# analog.net
KiCad netlist of a schematic drawn in Altium Designer
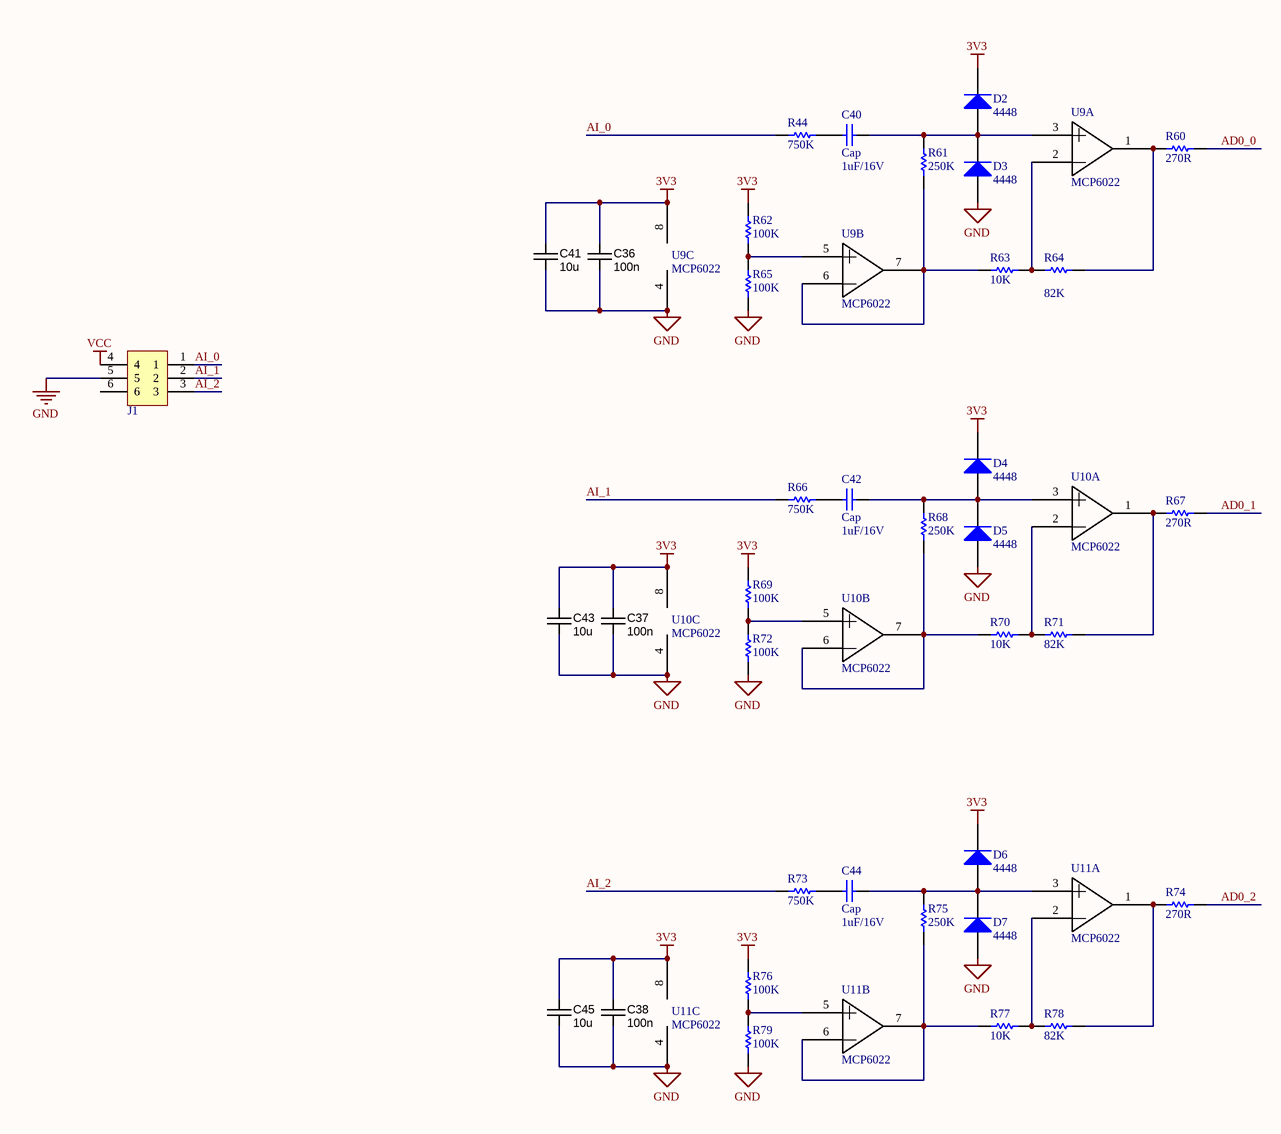
[diagram p0: analog.SchDoc]

(export (version "E")
  (design (tool "Eeschema 10.0.6"))
  (components
    (comp (ref "C36")
      (value "100n")
      (footprint "CAPC1005L")
      (description "Capacitor SMD")
      (fields (field (name "TOLERANCE") "?0%"))
      (libsource (lib "PBL - Capacitors") (part "CAPC_100n_0805"))
    )
    (comp (ref "C37")
      (value "100n")
      (footprint "CAPC1005L")
      (description "Capacitor SMD")
      (fields (field (name "TOLERANCE") "?0%"))
      (libsource (lib "PBL - Capacitors") (part "CAPC_100n_0805"))
    )
    (comp (ref "C38")
      (value "100n")
      (footprint "CAPC1005L")
      (description "Capacitor SMD")
      (fields (field (name "TOLERANCE") "?0%"))
      (libsource (lib "PBL - Capacitors") (part "CAPC_100n_0805"))
    )
    (comp (ref "C40")
      (value "Cap")
      (footprint "CAPC1005L")
      (description "Capacitor SMD")
      (fields (field (name "ALTIUM_VALUE") "1uF/16V") (field (name "PUBLISHER") "Altium Limited"))
      (libsource (lib "Miscellaneous Devices") (part "Cap"))
    )
    (comp (ref "C41")
      (value "10u")
      (footprint "CAPC2012N")
      (description "Capacitor SMD")
      (fields (field (name "TOLERANCE") "?0%"))
      (libsource (lib "PBL - Capacitors") (part "CAPC_100n_0805"))
    )
    (comp (ref "C42")
      (value "Cap")
      (footprint "CAPC1005L")
      (description "Capacitor SMD")
      (fields (field (name "ALTIUM_VALUE") "1uF/16V") (field (name "PUBLISHER") "Altium Limited"))
      (libsource (lib "Miscellaneous Devices") (part "Cap"))
    )
    (comp (ref "C43")
      (value "10u")
      (footprint "CAPC2012N")
      (description "Capacitor SMD")
      (fields (field (name "TOLERANCE") "?0%"))
      (libsource (lib "PBL - Capacitors") (part "CAPC_100n_0805"))
    )
    (comp (ref "C44")
      (value "Cap")
      (footprint "CAPC1005L")
      (description "Capacitor SMD")
      (fields (field (name "ALTIUM_VALUE") "1uF/16V") (field (name "PUBLISHER") "Altium Limited"))
      (libsource (lib "Miscellaneous Devices") (part "Cap"))
    )
    (comp (ref "C45")
      (value "10u")
      (footprint "CAPC2012N")
      (description "Capacitor SMD")
      (fields (field (name "TOLERANCE") "?0%"))
      (libsource (lib "PBL - Capacitors") (part "CAPC_100n_0805"))
    )
    (comp (ref "D2")
      (value "4448")
      (footprint "SOD323")
      (description "High Conductance Fast Diode")
      (fields (field (name "PUBLISHER") "Altium Limited"))
      (libsource (lib "Miscellaneous Devices") (part "Diode 1N4448"))
    )
    (comp (ref "D3")
      (value "4448")
      (footprint "SOD323")
      (description "High Conductance Fast Diode")
      (fields (field (name "PUBLISHER") "Altium Limited"))
      (libsource (lib "Miscellaneous Devices") (part "Diode 1N4448"))
    )
    (comp (ref "D4")
      (value "4448")
      (footprint "SOD323")
      (description "High Conductance Fast Diode")
      (fields (field (name "PUBLISHER") "Altium Limited"))
      (libsource (lib "Miscellaneous Devices") (part "Diode 1N4448"))
    )
    (comp (ref "D5")
      (value "4448")
      (footprint "SOD323")
      (description "High Conductance Fast Diode")
      (fields (field (name "PUBLISHER") "Altium Limited"))
      (libsource (lib "Miscellaneous Devices") (part "Diode 1N4448"))
    )
    (comp (ref "D6")
      (value "4448")
      (footprint "SOD323")
      (description "High Conductance Fast Diode")
      (fields (field (name "PUBLISHER") "Altium Limited"))
      (libsource (lib "Miscellaneous Devices") (part "Diode 1N4448"))
    )
    (comp (ref "D7")
      (value "4448")
      (footprint "SOD323")
      (description "High Conductance Fast Diode")
      (fields (field (name "PUBLISHER") "Altium Limited"))
      (libsource (lib "Miscellaneous Devices") (part "Diode 1N4448"))
    )
    (comp (ref "J1")
      (value "2X6du pont-2.0mm-6line to 90der")
      (footprint "HDR2X3 - duplicate-6-line 90 der")
      (libsource (lib "All_Library1") (part "2X6du pont-2.0mm-6line to 90der"))
    )
    (comp (ref "R44")
      (value "750K")
      (footprint "RESC1005L")
      (description "Resistor SMD")
      (fields (field (name "PUBLISHER") "Altium Limited"))
      (libsource (lib "Miscellaneous Devices") (part "Res1"))
    )
    (comp (ref "R60")
      (value "270R")
      (footprint "RESC1005L")
      (description "Resistor SMD")
      (fields (field (name "PUBLISHER") "Altium Limited"))
      (libsource (lib "Miscellaneous Devices") (part "Res1"))
    )
    (comp (ref "R61")
      (value "250K")
      (footprint "RESC1005L")
      (description "Resistor SMD")
      (fields (field (name "PUBLISHER") "Altium Limited"))
      (libsource (lib "Miscellaneous Devices") (part "Res1"))
    )
    (comp (ref "R62")
      (value "100K")
      (footprint "RESC1005L")
      (description "Resistor SMD")
      (fields (field (name "PUBLISHER") "Altium Limited"))
      (libsource (lib "Miscellaneous Devices") (part "Res1"))
    )
    (comp (ref "R63")
      (value "10K")
      (footprint "RESC1005L")
      (description "Resistor SMD")
      (fields (field (name "PUBLISHER") "Altium Limited"))
      (libsource (lib "Miscellaneous Devices") (part "Res1"))
    )
    (comp (ref "R64")
      (value "82K")
      (footprint "RESC1005L")
      (description "Resistor SMD")
      (fields (field (name "PUBLISHER") "Altium Limited"))
      (libsource (lib "Miscellaneous Devices") (part "Res1"))
    )
    (comp (ref "R65")
      (value "100K")
      (footprint "RESC1005L")
      (description "Resistor SMD")
      (fields (field (name "PUBLISHER") "Altium Limited"))
      (libsource (lib "Miscellaneous Devices") (part "Res1"))
    )
    (comp (ref "R66")
      (value "750K")
      (footprint "RESC1005L")
      (description "Resistor SMD")
      (fields (field (name "PUBLISHER") "Altium Limited"))
      (libsource (lib "Miscellaneous Devices") (part "Res1"))
    )
    (comp (ref "R67")
      (value "270R")
      (footprint "RESC1005L")
      (description "Resistor SMD")
      (fields (field (name "PUBLISHER") "Altium Limited"))
      (libsource (lib "Miscellaneous Devices") (part "Res1"))
    )
    (comp (ref "R68")
      (value "250K")
      (footprint "RESC1005L")
      (description "Resistor SMD")
      (fields (field (name "PUBLISHER") "Altium Limited"))
      (libsource (lib "Miscellaneous Devices") (part "Res1"))
    )
    (comp (ref "R69")
      (value "100K")
      (footprint "RESC1005L")
      (description "Resistor SMD")
      (fields (field (name "PUBLISHER") "Altium Limited"))
      (libsource (lib "Miscellaneous Devices") (part "Res1"))
    )
    (comp (ref "R70")
      (value "10K")
      (footprint "RESC1005L")
      (description "Resistor SMD")
      (fields (field (name "PUBLISHER") "Altium Limited"))
      (libsource (lib "Miscellaneous Devices") (part "Res1"))
    )
    (comp (ref "R71")
      (value "82K")
      (footprint "RESC1005L")
      (description "Resistor SMD")
      (fields (field (name "PUBLISHER") "Altium Limited"))
      (libsource (lib "Miscellaneous Devices") (part "Res1"))
    )
    (comp (ref "R72")
      (value "100K")
      (footprint "RESC1005L")
      (description "Resistor SMD")
      (fields (field (name "PUBLISHER") "Altium Limited"))
      (libsource (lib "Miscellaneous Devices") (part "Res1"))
    )
    (comp (ref "R73")
      (value "750K")
      (footprint "RESC1005L")
      (description "Resistor SMD")
      (fields (field (name "PUBLISHER") "Altium Limited"))
      (libsource (lib "Miscellaneous Devices") (part "Res1"))
    )
    (comp (ref "R74")
      (value "270R")
      (footprint "RESC1005L")
      (description "Resistor SMD")
      (fields (field (name "PUBLISHER") "Altium Limited"))
      (libsource (lib "Miscellaneous Devices") (part "Res1"))
    )
    (comp (ref "R75")
      (value "250K")
      (footprint "RESC1005L")
      (description "Resistor SMD")
      (fields (field (name "PUBLISHER") "Altium Limited"))
      (libsource (lib "Miscellaneous Devices") (part "Res1"))
    )
    (comp (ref "R76")
      (value "100K")
      (footprint "RESC1005L")
      (description "Resistor SMD")
      (fields (field (name "PUBLISHER") "Altium Limited"))
      (libsource (lib "Miscellaneous Devices") (part "Res1"))
    )
    (comp (ref "R77")
      (value "10K")
      (footprint "RESC1005L")
      (description "Resistor SMD")
      (fields (field (name "PUBLISHER") "Altium Limited"))
      (libsource (lib "Miscellaneous Devices") (part "Res1"))
    )
    (comp (ref "R78")
      (value "82K")
      (footprint "RESC1005L")
      (description "Resistor SMD")
      (fields (field (name "PUBLISHER") "Altium Limited"))
      (libsource (lib "Miscellaneous Devices") (part "Res1"))
    )
    (comp (ref "R79")
      (value "100K")
      (footprint "RESC1005L")
      (description "Resistor SMD")
      (fields (field (name "PUBLISHER") "Altium Limited"))
      (libsource (lib "Miscellaneous Devices") (part "Res1"))
    )
    (comp (ref "U9") (value "MCP6022") (footprint "TSSOP-ST8_N") (libsource (lib "Schlib1") (part "MCP6022")))
    (comp (ref "U10")
      (value "MCP6022")
      (footprint "TSSOP-ST8_N")
      (libsource (lib "Schlib1") (part "MCP6022"))
    )
    (comp (ref "U11")
      (value "MCP6022")
      (footprint "TSSOP-ST8_N")
      (libsource (lib "Schlib1") (part "MCP6022"))
    )
  )
  (nets
    (net (code "1") (name "/AD0_0") (class "Default")
      (node (ref "R60") (pin "2") (pinfunction "2_2") (pintype "passive"))
    )
    (net (code "2") (name "/AD0_1") (class "Default")
      (node (ref "R67") (pin "2") (pinfunction "2_2") (pintype "passive"))
    )
    (net (code "3") (name "/AD0_2") (class "Default")
      (node (ref "R74") (pin "2") (pinfunction "2_2") (pintype "passive"))
    )
    (net (code "4") (name "/AI_0") (class "Default")
      (node (ref "J1") (pin "1") (pinfunction "1_1") (pintype "passive"))
      (node (ref "R44") (pin "1") (pinfunction "1_1") (pintype "passive"))
    )
    (net (code "5") (name "/AI_1") (class "Default")
      (node (ref "J1") (pin "2") (pinfunction "2_2") (pintype "passive"))
      (node (ref "R66") (pin "1") (pinfunction "1_1") (pintype "passive"))
    )
    (net (code "6") (name "/AI_2") (class "Default")
      (node (ref "J1") (pin "3") (pinfunction "3_3") (pintype "passive"))
      (node (ref "R73") (pin "1") (pinfunction "1_1") (pintype "passive"))
    )
    (net (code "7") (name "3V3") (class "Default")
      (node (ref "C36") (pin "1") (pintype "passive"))
      (node (ref "C37") (pin "1") (pintype "passive"))
      (node (ref "C38") (pin "1") (pintype "passive"))
      (node (ref "C41") (pin "1") (pintype "passive"))
      (node (ref "C43") (pin "1") (pintype "passive"))
      (node (ref "C45") (pin "1") (pintype "passive"))
      (node (ref "D2") (pin "2") (pinfunction "K_2") (pintype "passive"))
      (node (ref "D4") (pin "2") (pinfunction "K_2") (pintype "passive"))
      (node (ref "D6") (pin "2") (pinfunction "K_2") (pintype "passive"))
      (node (ref "R62") (pin "2") (pinfunction "2_2") (pintype "passive"))
      (node (ref "R69") (pin "2") (pinfunction "2_2") (pintype "passive"))
      (node (ref "R76") (pin "2") (pinfunction "2_2") (pintype "passive"))
      (node (ref "U10") (pin "8") (pinfunction "VDD_8") (pintype "passive"))
      (node (ref "U11") (pin "8") (pinfunction "VDD_8") (pintype "passive"))
      (node (ref "U9") (pin "8") (pinfunction "VDD_8") (pintype "passive"))
    )
    (net (code "8") (name "GND") (class "Default")
      (node (ref "C36") (pin "2") (pintype "passive"))
      (node (ref "C37") (pin "2") (pintype "passive"))
      (node (ref "C38") (pin "2") (pintype "passive"))
      (node (ref "C41") (pin "2") (pintype "passive"))
      (node (ref "C43") (pin "2") (pintype "passive"))
      (node (ref "C45") (pin "2") (pintype "passive"))
      (node (ref "D3") (pin "1") (pinfunction "A_1") (pintype "passive"))
      (node (ref "D5") (pin "1") (pinfunction "A_1") (pintype "passive"))
      (node (ref "D7") (pin "1") (pinfunction "A_1") (pintype "passive"))
      (node (ref "J1") (pin "5") (pinfunction "5_5") (pintype "passive"))
      (node (ref "R65") (pin "1") (pinfunction "1_1") (pintype "passive"))
      (node (ref "R72") (pin "1") (pinfunction "1_1") (pintype "passive"))
      (node (ref "R79") (pin "1") (pinfunction "1_1") (pintype "passive"))
      (node (ref "U10") (pin "4") (pinfunction "GND_4") (pintype "passive"))
      (node (ref "U11") (pin "4") (pinfunction "GND_4") (pintype "passive"))
      (node (ref "U9") (pin "4") (pinfunction "GND_4") (pintype "passive"))
    )
    (net (code "9") (name "Net-(C40-Pad1)") (class "Default")
      (node (ref "C40") (pin "1") (pinfunction "1_1") (pintype "passive"))
      (node (ref "R44") (pin "2") (pinfunction "2_2") (pintype "passive"))
    )
    (net (code "10") (name "Net-(C42-Pad1)") (class "Default")
      (node (ref "C42") (pin "1") (pinfunction "1_1") (pintype "passive"))
      (node (ref "R66") (pin "2") (pinfunction "2_2") (pintype "passive"))
    )
    (net (code "11") (name "Net-(C44-Pad1)") (class "Default")
      (node (ref "C44") (pin "1") (pinfunction "1_1") (pintype "passive"))
      (node (ref "R73") (pin "2") (pinfunction "2_2") (pintype "passive"))
    )
    (net (code "12") (name "Net-(D2-A)") (class "Default")
      (node (ref "C40") (pin "2") (pinfunction "2_2") (pintype "passive"))
      (node (ref "D2") (pin "1") (pinfunction "A_1") (pintype "passive"))
      (node (ref "D3") (pin "2") (pinfunction "K_2") (pintype "passive"))
      (node (ref "R61") (pin "2") (pinfunction "2_2") (pintype "passive"))
      (node (ref "U9") (pin "3") (pinfunction "VINA+_3") (pintype "passive"))
    )
    (net (code "13") (name "Net-(D4-A)") (class "Default")
      (node (ref "C42") (pin "2") (pinfunction "2_2") (pintype "passive"))
      (node (ref "D4") (pin "1") (pinfunction "A_1") (pintype "passive"))
      (node (ref "D5") (pin "2") (pinfunction "K_2") (pintype "passive"))
      (node (ref "R68") (pin "2") (pinfunction "2_2") (pintype "passive"))
      (node (ref "U10") (pin "3") (pinfunction "VINA+_3") (pintype "passive"))
    )
    (net (code "14") (name "Net-(D6-A)") (class "Default")
      (node (ref "C44") (pin "2") (pinfunction "2_2") (pintype "passive"))
      (node (ref "D6") (pin "1") (pinfunction "A_1") (pintype "passive"))
      (node (ref "D7") (pin "2") (pinfunction "K_2") (pintype "passive"))
      (node (ref "R75") (pin "2") (pinfunction "2_2") (pintype "passive"))
      (node (ref "U11") (pin "3") (pinfunction "VINA+_3") (pintype "passive"))
    )
    (net (code "15") (name "Net-(U9A-VINA-)") (class "Default")
      (node (ref "R63") (pin "2") (pinfunction "2_2") (pintype "passive"))
      (node (ref "R64") (pin "1") (pinfunction "1_1") (pintype "passive"))
      (node (ref "U9") (pin "2") (pinfunction "VINA-_2") (pintype "passive"))
    )
    (net (code "16") (name "Net-(U9A-VOUTA)") (class "Default")
      (node (ref "R60") (pin "1") (pinfunction "1_1") (pintype "passive"))
      (node (ref "R64") (pin "2") (pinfunction "2_2") (pintype "passive"))
      (node (ref "U9") (pin "1") (pinfunction "VOUTA_1") (pintype "passive"))
    )
    (net (code "17") (name "Net-(U9B-VINB+)") (class "Default")
      (node (ref "R62") (pin "1") (pinfunction "1_1") (pintype "passive"))
      (node (ref "R65") (pin "2") (pinfunction "2_2") (pintype "passive"))
      (node (ref "U9") (pin "5") (pinfunction "VINB+_5") (pintype "passive"))
    )
    (net (code "18") (name "Net-(U9B-VINB-)") (class "Default")
      (node (ref "R61") (pin "1") (pinfunction "1_1") (pintype "passive"))
      (node (ref "R63") (pin "1") (pinfunction "1_1") (pintype "passive"))
      (node (ref "U9") (pin "6") (pinfunction "VINB-_6") (pintype "passive"))
      (node (ref "U9") (pin "7") (pinfunction "VOUTB_7") (pintype "passive"))
    )
    (net (code "19") (name "Net-(U10A-VINA-)") (class "Default")
      (node (ref "R70") (pin "2") (pinfunction "2_2") (pintype "passive"))
      (node (ref "R71") (pin "1") (pinfunction "1_1") (pintype "passive"))
      (node (ref "U10") (pin "2") (pinfunction "VINA-_2") (pintype "passive"))
    )
    (net (code "20") (name "Net-(U10A-VOUTA)") (class "Default")
      (node (ref "R67") (pin "1") (pinfunction "1_1") (pintype "passive"))
      (node (ref "R71") (pin "2") (pinfunction "2_2") (pintype "passive"))
      (node (ref "U10") (pin "1") (pinfunction "VOUTA_1") (pintype "passive"))
    )
    (net (code "21") (name "Net-(U10B-VINB+)") (class "Default")
      (node (ref "R69") (pin "1") (pinfunction "1_1") (pintype "passive"))
      (node (ref "R72") (pin "2") (pinfunction "2_2") (pintype "passive"))
      (node (ref "U10") (pin "5") (pinfunction "VINB+_5") (pintype "passive"))
    )
    (net (code "22") (name "Net-(U10B-VINB-)") (class "Default")
      (node (ref "R68") (pin "1") (pinfunction "1_1") (pintype "passive"))
      (node (ref "R70") (pin "1") (pinfunction "1_1") (pintype "passive"))
      (node (ref "U10") (pin "6") (pinfunction "VINB-_6") (pintype "passive"))
      (node (ref "U10") (pin "7") (pinfunction "VOUTB_7") (pintype "passive"))
    )
    (net (code "23") (name "Net-(U11A-VINA-)") (class "Default")
      (node (ref "R77") (pin "2") (pinfunction "2_2") (pintype "passive"))
      (node (ref "R78") (pin "1") (pinfunction "1_1") (pintype "passive"))
      (node (ref "U11") (pin "2") (pinfunction "VINA-_2") (pintype "passive"))
    )
    (net (code "24") (name "Net-(U11A-VOUTA)") (class "Default")
      (node (ref "R74") (pin "1") (pinfunction "1_1") (pintype "passive"))
      (node (ref "R78") (pin "2") (pinfunction "2_2") (pintype "passive"))
      (node (ref "U11") (pin "1") (pinfunction "VOUTA_1") (pintype "passive"))
    )
    (net (code "25") (name "Net-(U11B-VINB+)") (class "Default")
      (node (ref "R76") (pin "1") (pinfunction "1_1") (pintype "passive"))
      (node (ref "R79") (pin "2") (pinfunction "2_2") (pintype "passive"))
      (node (ref "U11") (pin "5") (pinfunction "VINB+_5") (pintype "passive"))
    )
    (net (code "26") (name "Net-(U11B-VINB-)") (class "Default")
      (node (ref "R75") (pin "1") (pinfunction "1_1") (pintype "passive"))
      (node (ref "R77") (pin "1") (pinfunction "1_1") (pintype "passive"))
      (node (ref "U11") (pin "6") (pinfunction "VINB-_6") (pintype "passive"))
      (node (ref "U11") (pin "7") (pinfunction "VOUTB_7") (pintype "passive"))
    )
    (net (code "27") (name "VCC") (class "Default")
      (node (ref "J1") (pin "4") (pinfunction "4_4") (pintype "passive"))
    )
    (net (code "28") (name "unconnected-(J1-Pad6)") (class "Default")
      (node (ref "J1") (pin "6") (pinfunction "6_6") (pintype "passive"))
    )
  )
)
